# 8500_ADC_Y.net
KiCad netlist of a schematic drawn in Altium Designer
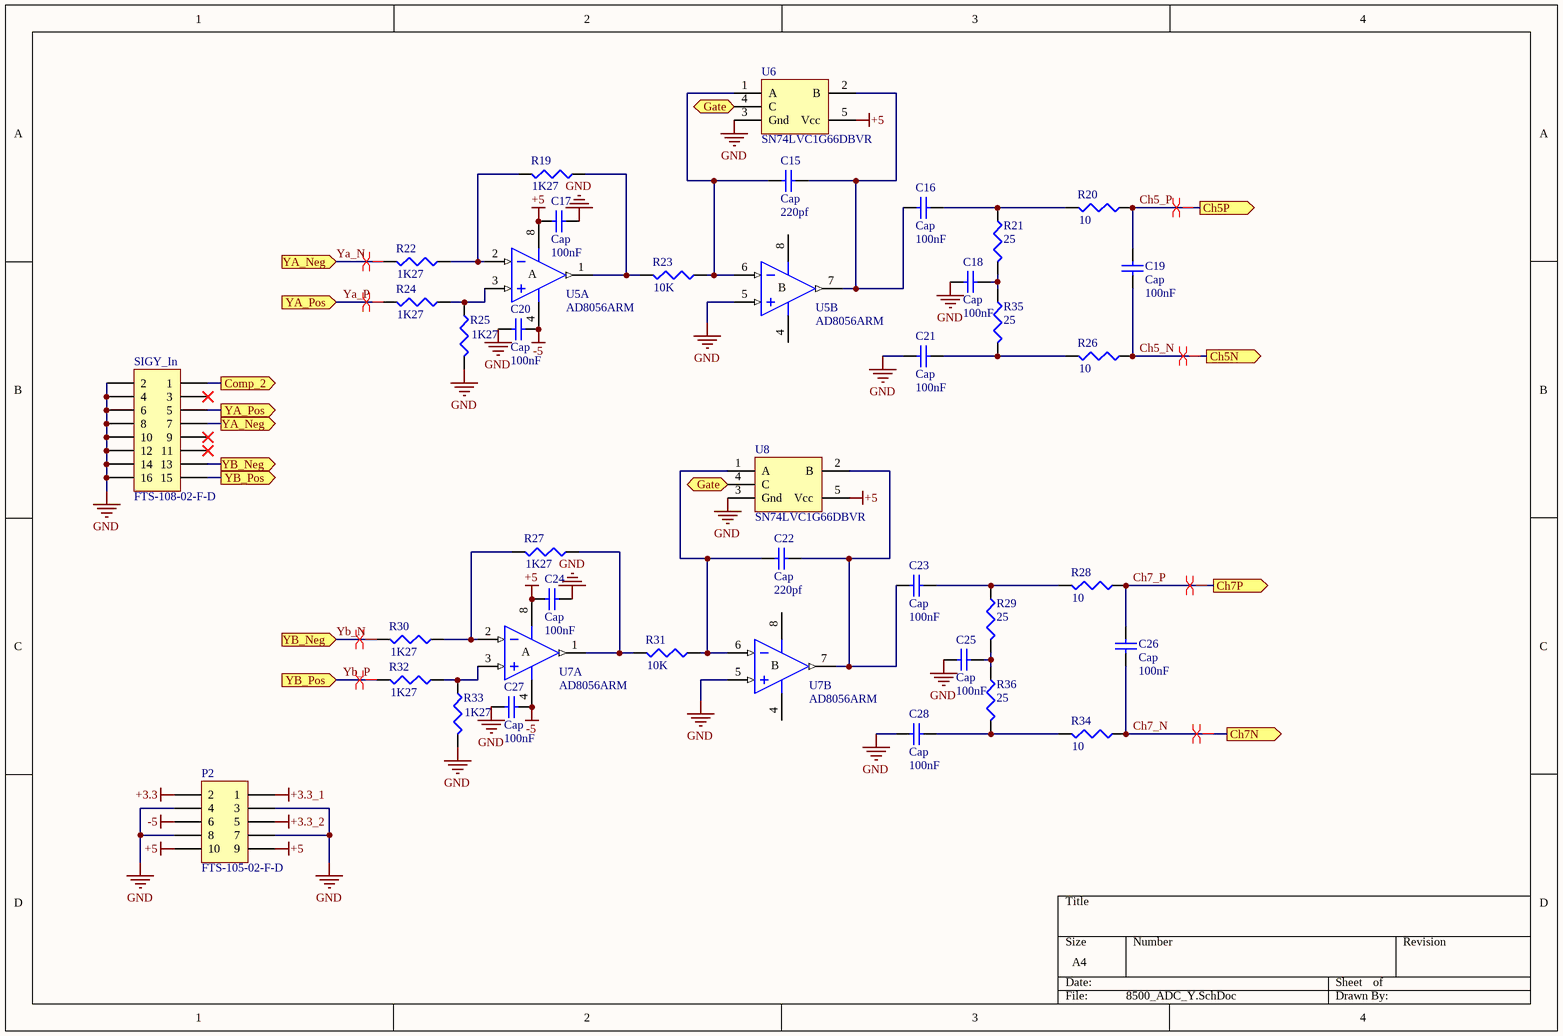
[diagram p0: 8500_ADC_Y.SchDoc]

(export (version "E")
  (design (tool "Eeschema 10.0.6"))
  (components
    (comp (ref "C15")
      (value "Cap")
      (footprint "0402")
      (description "Capacitor")
      (fields (field (name "ALTIUM_VALUE") "220pf") (field (name "PUBLISHER") "Altium Limited"))
      (libsource (lib "Miscellaneous Devices") (part "Cap"))
    )
    (comp (ref "C16")
      (value "Cap")
      (footprint "0402")
      (description "Capacitor")
      (fields (field (name "ALTIUM_VALUE") "100nF") (field (name "PUBLISHER") "Altium Limited"))
      (libsource (lib "Miscellaneous Devices") (part "Cap"))
    )
    (comp (ref "C17")
      (value "Cap")
      (footprint "0402")
      (description "Capacitor")
      (fields (field (name "ALTIUM_VALUE") "100nF") (field (name "PUBLISHER") "Altium Limited"))
      (libsource (lib "Miscellaneous Devices") (part "Cap"))
    )
    (comp (ref "C18")
      (value "Cap")
      (footprint "0402")
      (description "Capacitor")
      (fields (field (name "ALTIUM_VALUE") "100nF") (field (name "PUBLISHER") "Altium Limited"))
      (libsource (lib "Miscellaneous Devices") (part "Cap"))
    )
    (comp (ref "C19")
      (value "Cap")
      (footprint "0402")
      (description "Capacitor")
      (fields (field (name "ALTIUM_VALUE") "100nF") (field (name "PUBLISHER") "Altium Limited"))
      (libsource (lib "Miscellaneous Devices") (part "Cap"))
    )
    (comp (ref "C20")
      (value "Cap")
      (footprint "0402")
      (description "Capacitor")
      (fields (field (name "ALTIUM_VALUE") "100nF") (field (name "PUBLISHER") "Altium Limited"))
      (libsource (lib "Miscellaneous Devices") (part "Cap"))
    )
    (comp (ref "C21")
      (value "Cap")
      (footprint "0402")
      (description "Capacitor")
      (fields (field (name "ALTIUM_VALUE") "100nF") (field (name "PUBLISHER") "Altium Limited"))
      (libsource (lib "Miscellaneous Devices") (part "Cap"))
    )
    (comp (ref "C22")
      (value "Cap")
      (footprint "0402")
      (description "Capacitor")
      (fields (field (name "ALTIUM_VALUE") "220pf") (field (name "PUBLISHER") "Altium Limited"))
      (libsource (lib "Miscellaneous Devices") (part "Cap"))
    )
    (comp (ref "C23")
      (value "Cap")
      (footprint "0402")
      (description "Capacitor")
      (fields (field (name "ALTIUM_VALUE") "100nF") (field (name "PUBLISHER") "Altium Limited"))
      (libsource (lib "Miscellaneous Devices") (part "Cap"))
    )
    (comp (ref "C24")
      (value "Cap")
      (footprint "0402")
      (description "Capacitor")
      (fields (field (name "ALTIUM_VALUE") "100nF") (field (name "PUBLISHER") "Altium Limited"))
      (libsource (lib "Miscellaneous Devices") (part "Cap"))
    )
    (comp (ref "C25")
      (value "Cap")
      (footprint "0402")
      (description "Capacitor")
      (fields (field (name "ALTIUM_VALUE") "100nF") (field (name "PUBLISHER") "Altium Limited"))
      (libsource (lib "Miscellaneous Devices") (part "Cap"))
    )
    (comp (ref "C26")
      (value "Cap")
      (footprint "0402")
      (description "Capacitor")
      (fields (field (name "ALTIUM_VALUE") "100nF") (field (name "PUBLISHER") "Altium Limited"))
      (libsource (lib "Miscellaneous Devices") (part "Cap"))
    )
    (comp (ref "C27")
      (value "Cap")
      (footprint "0402")
      (description "Capacitor")
      (fields (field (name "ALTIUM_VALUE") "100nF") (field (name "PUBLISHER") "Altium Limited"))
      (libsource (lib "Miscellaneous Devices") (part "Cap"))
    )
    (comp (ref "C28")
      (value "Cap")
      (footprint "0402")
      (description "Capacitor")
      (fields (field (name "ALTIUM_VALUE") "100nF") (field (name "PUBLISHER") "Altium Limited"))
      (libsource (lib "Miscellaneous Devices") (part "Cap"))
    )
    (comp (ref "P2")
      (value "FTS-105-02-F-D")
      (footprint "MHDR2X5")
      (libsource (lib "Int_Lib1") (part "FTR-105-01-D"))
    )
    (comp (ref "R19")
      (value "1K27")
      (footprint "0402")
      (description "Resistor")
      (fields (field (name "Comment") "Res3") (field (name "PUBLISHER") "Altium Limited"))
      (libsource (lib "Miscellaneous Devices") (part "Res3"))
    )
    (comp (ref "R20")
      (value "10")
      (footprint "0402")
      (description "Resistor")
      (fields (field (name "Comment") "Res3") (field (name "PUBLISHER") "Altium Limited"))
      (libsource (lib "Miscellaneous Devices") (part "Res3"))
    )
    (comp (ref "R21")
      (value "25")
      (footprint "0402")
      (description "Resistor")
      (fields (field (name "Comment") "Res3") (field (name "PUBLISHER") "Altium Limited"))
      (libsource (lib "Miscellaneous Devices") (part "Res3"))
    )
    (comp (ref "R22")
      (value "1K27")
      (footprint "0402")
      (description "Resistor")
      (fields (field (name "Comment") "Res3") (field (name "PUBLISHER") "Altium Limited"))
      (libsource (lib "Miscellaneous Devices") (part "Res3"))
    )
    (comp (ref "R23")
      (value "10K")
      (footprint "0402")
      (description "Resistor")
      (fields (field (name "Comment") "Res3") (field (name "PUBLISHER") "Altium Limited"))
      (libsource (lib "Miscellaneous Devices") (part "Res3"))
    )
    (comp (ref "R24")
      (value "1K27")
      (footprint "0402")
      (description "Resistor")
      (fields (field (name "Comment") "Res3") (field (name "PUBLISHER") "Altium Limited"))
      (libsource (lib "Miscellaneous Devices") (part "Res3"))
    )
    (comp (ref "R25")
      (value "1K27")
      (footprint "0402")
      (description "Resistor")
      (fields (field (name "Comment") "Res3") (field (name "PUBLISHER") "Altium Limited"))
      (libsource (lib "Miscellaneous Devices") (part "Res3"))
    )
    (comp (ref "R26")
      (value "10")
      (footprint "0402")
      (description "Resistor")
      (fields (field (name "Comment") "Res3") (field (name "PUBLISHER") "Altium Limited"))
      (libsource (lib "Miscellaneous Devices") (part "Res3"))
    )
    (comp (ref "R27")
      (value "1K27")
      (footprint "0402")
      (description "Resistor")
      (fields (field (name "Comment") "Res3") (field (name "PUBLISHER") "Altium Limited"))
      (libsource (lib "Miscellaneous Devices") (part "Res3"))
    )
    (comp (ref "R28")
      (value "10")
      (footprint "0402")
      (description "Resistor")
      (fields (field (name "Comment") "Res3") (field (name "PUBLISHER") "Altium Limited"))
      (libsource (lib "Miscellaneous Devices") (part "Res3"))
    )
    (comp (ref "R29")
      (value "25")
      (footprint "0402")
      (description "Resistor")
      (fields (field (name "Comment") "Res3") (field (name "PUBLISHER") "Altium Limited"))
      (libsource (lib "Miscellaneous Devices") (part "Res3"))
    )
    (comp (ref "R30")
      (value "1K27")
      (footprint "0402")
      (description "Resistor")
      (fields (field (name "Comment") "Res3") (field (name "PUBLISHER") "Altium Limited"))
      (libsource (lib "Miscellaneous Devices") (part "Res3"))
    )
    (comp (ref "R31")
      (value "10K")
      (footprint "0402")
      (description "Resistor")
      (fields (field (name "Comment") "Res3") (field (name "PUBLISHER") "Altium Limited"))
      (libsource (lib "Miscellaneous Devices") (part "Res3"))
    )
    (comp (ref "R32")
      (value "1K27")
      (footprint "0402")
      (description "Resistor")
      (fields (field (name "Comment") "Res3") (field (name "PUBLISHER") "Altium Limited"))
      (libsource (lib "Miscellaneous Devices") (part "Res3"))
    )
    (comp (ref "R33")
      (value "1K27")
      (footprint "0402")
      (description "Resistor")
      (fields (field (name "Comment") "Res3") (field (name "PUBLISHER") "Altium Limited"))
      (libsource (lib "Miscellaneous Devices") (part "Res3"))
    )
    (comp (ref "R34")
      (value "10")
      (footprint "0402")
      (description "Resistor")
      (fields (field (name "Comment") "Res3") (field (name "PUBLISHER") "Altium Limited"))
      (libsource (lib "Miscellaneous Devices") (part "Res3"))
    )
    (comp (ref "R35")
      (value "25")
      (footprint "0402")
      (description "Resistor")
      (fields (field (name "Comment") "Res3") (field (name "PUBLISHER") "Altium Limited"))
      (libsource (lib "Miscellaneous Devices") (part "Res3"))
    )
    (comp (ref "R36")
      (value "25")
      (footprint "0402")
      (description "Resistor")
      (fields (field (name "Comment") "Res3") (field (name "PUBLISHER") "Altium Limited"))
      (libsource (lib "Miscellaneous Devices") (part "Res3"))
    )
    (comp (ref "SIGY_In")
      (value "FTS-108-02-F-D")
      (footprint "MHDR2X8")
      (libsource (lib "Int_Lib1") (part "FTR-108-01-D"))
    )
    (comp (ref "U5")
      (value "AD8056ARM")
      (footprint "RM-8")
      (description "Low Cost, 300MHz Voltage Feedback Amplifier")
      (fields (field (name "PUBLISHER") "Altium Limited"))
      (libsource (lib "AD Operational Amplifier") (part "AD8056ARM"))
    )
    (comp (ref "U6")
      (value "SN74LVC1G66DBVR")
      (footprint "SOT23-5")
      (libsource (lib "Int_Lib1") (part "SN74LVC1G66DBVR"))
    )
    (comp (ref "U7")
      (value "AD8056ARM")
      (footprint "RM-8")
      (description "Low Cost, 300MHz Voltage Feedback Amplifier")
      (fields (field (name "PUBLISHER") "Altium Limited"))
      (libsource (lib "AD Operational Amplifier") (part "AD8056ARM"))
    )
    (comp (ref "U8")
      (value "SN74LVC1G66DBVR")
      (footprint "SOT23-5")
      (libsource (lib "Int_Lib1") (part "SN74LVC1G66DBVR"))
    )
  )
  (nets
    (net (code "1") (name "+3.3") (class "Default")
      (node (ref "P2") (pin "2") (pinfunction "2_2") (pintype "passive"))
    )
    (net (code "2") (name "+3.3_1") (class "Default")
      (node (ref "P2") (pin "1") (pinfunction "1_1") (pintype "passive"))
    )
    (net (code "3") (name "+3.3_2") (class "Default")
      (node (ref "P2") (pin "5") (pinfunction "5_5") (pintype "passive"))
    )
    (net (code "4") (name "+5") (class "Default")
      (node (ref "C17") (pin "1") (pinfunction "1_1") (pintype "passive"))
      (node (ref "C24") (pin "1") (pinfunction "1_1") (pintype "passive"))
      (node (ref "P2") (pin "10") (pinfunction "10_10") (pintype "passive"))
      (node (ref "P2") (pin "9") (pinfunction "9_9") (pintype "passive"))
      (node (ref "U5") (pin "8") (pinfunction "V+_8") (pintype "power_in"))
      (node (ref "U6") (pin "5") (pinfunction "Vcc_5") (pintype "passive"))
      (node (ref "U7") (pin "8") (pinfunction "V+_8") (pintype "power_in"))
      (node (ref "U8") (pin "5") (pinfunction "Vcc_5") (pintype "passive"))
    )
    (net (code "5") (name "-5") (class "Default")
      (node (ref "C20") (pin "2") (pinfunction "2_2") (pintype "passive"))
      (node (ref "C27") (pin "2") (pinfunction "2_2") (pintype "passive"))
      (node (ref "P2") (pin "6") (pinfunction "6_6") (pintype "passive"))
      (node (ref "U5") (pin "4") (pinfunction "V-_4") (pintype "power_in"))
      (node (ref "U7") (pin "4") (pinfunction "V-_4") (pintype "power_in"))
    )
    (net (code "6") (name "/Ch5_N") (class "Default")
      (node (ref "C19") (pin "1") (pinfunction "1_1") (pintype "passive"))
      (node (ref "R26") (pin "1") (pinfunction "1_1") (pintype "passive"))
    )
    (net (code "7") (name "/Ch5_P") (class "Default")
      (node (ref "C19") (pin "2") (pinfunction "2_2") (pintype "passive"))
      (node (ref "R20") (pin "1") (pinfunction "1_1") (pintype "passive"))
    )
    (net (code "8") (name "/Ch7_N") (class "Default")
      (node (ref "C26") (pin "1") (pinfunction "1_1") (pintype "passive"))
      (node (ref "R34") (pin "1") (pinfunction "1_1") (pintype "passive"))
    )
    (net (code "9") (name "/Ch7_P") (class "Default")
      (node (ref "C26") (pin "2") (pinfunction "2_2") (pintype "passive"))
      (node (ref "R28") (pin "1") (pinfunction "1_1") (pintype "passive"))
    )
    (net (code "10") (name "/Comp_2") (class "Default")
      (node (ref "SIGY_In") (pin "1") (pinfunction "1_1") (pintype "passive"))
    )
    (net (code "11") (name "/Gate") (class "Default")
      (node (ref "U6") (pin "4") (pinfunction "C_4") (pintype "passive"))
      (node (ref "U8") (pin "4") (pinfunction "C_4") (pintype "passive"))
    )
    (net (code "12") (name "/Ya_N") (class "Default")
      (node (ref "R22") (pin "2") (pinfunction "2_2") (pintype "passive"))
      (node (ref "SIGY_In") (pin "7") (pinfunction "7_7") (pintype "passive"))
    )
    (net (code "13") (name "/Ya_P") (class "Default")
      (node (ref "R24") (pin "2") (pinfunction "2_2") (pintype "passive"))
      (node (ref "SIGY_In") (pin "5") (pinfunction "5_5") (pintype "passive"))
    )
    (net (code "14") (name "/Yb_N") (class "Default")
      (node (ref "R30") (pin "2") (pinfunction "2_2") (pintype "passive"))
      (node (ref "SIGY_In") (pin "13") (pinfunction "13_13") (pintype "passive"))
    )
    (net (code "15") (name "/Yb_P") (class "Default")
      (node (ref "R32") (pin "2") (pinfunction "2_2") (pintype "passive"))
      (node (ref "SIGY_In") (pin "15") (pinfunction "15_15") (pintype "passive"))
    )
    (net (code "16") (name "GND") (class "Default")
      (node (ref "C17") (pin "2") (pinfunction "2_2") (pintype "passive"))
      (node (ref "C18") (pin "1") (pinfunction "1_1") (pintype "passive"))
      (node (ref "C20") (pin "1") (pinfunction "1_1") (pintype "passive"))
      (node (ref "C21") (pin "1") (pinfunction "1_1") (pintype "passive"))
      (node (ref "C24") (pin "2") (pinfunction "2_2") (pintype "passive"))
      (node (ref "C25") (pin "1") (pinfunction "1_1") (pintype "passive"))
      (node (ref "C27") (pin "1") (pinfunction "1_1") (pintype "passive"))
      (node (ref "C28") (pin "1") (pinfunction "1_1") (pintype "passive"))
      (node (ref "P2") (pin "3") (pinfunction "3_3") (pintype "passive"))
      (node (ref "P2") (pin "4") (pinfunction "4_4") (pintype "passive"))
      (node (ref "P2") (pin "7") (pinfunction "7_7") (pintype "passive"))
      (node (ref "P2") (pin "8") (pinfunction "8_8") (pintype "passive"))
      (node (ref "R25") (pin "2") (pinfunction "2_2") (pintype "passive"))
      (node (ref "R33") (pin "2") (pinfunction "2_2") (pintype "passive"))
      (node (ref "SIGY_In") (pin "10") (pinfunction "10_10") (pintype "passive"))
      (node (ref "SIGY_In") (pin "12") (pinfunction "12_12") (pintype "passive"))
      (node (ref "SIGY_In") (pin "14") (pinfunction "14_14") (pintype "passive"))
      (node (ref "SIGY_In") (pin "16") (pinfunction "16_16") (pintype "passive"))
      (node (ref "SIGY_In") (pin "2") (pinfunction "2_2") (pintype "passive"))
      (node (ref "SIGY_In") (pin "4") (pinfunction "4_4") (pintype "passive"))
      (node (ref "SIGY_In") (pin "6") (pinfunction "6_6") (pintype "passive"))
      (node (ref "SIGY_In") (pin "8") (pinfunction "8_8") (pintype "passive"))
      (node (ref "U5") (pin "5") (pinfunction "IN+_5") (pintype "input"))
      (node (ref "U6") (pin "3") (pinfunction "Gnd_3") (pintype "passive"))
      (node (ref "U7") (pin "5") (pinfunction "IN+_5") (pintype "input"))
      (node (ref "U8") (pin "3") (pinfunction "Gnd_3") (pintype "passive"))
    )
    (net (code "17") (name "Net-(C16-Pad2)") (class "Default")
      (node (ref "C16") (pin "2") (pinfunction "2_2") (pintype "passive"))
      (node (ref "R20") (pin "2") (pinfunction "2_2") (pintype "passive"))
      (node (ref "R21") (pin "1") (pinfunction "1_1") (pintype "passive"))
    )
    (net (code "18") (name "Net-(C18-Pad2)") (class "Default")
      (node (ref "C18") (pin "2") (pinfunction "2_2") (pintype "passive"))
      (node (ref "R21") (pin "2") (pinfunction "2_2") (pintype "passive"))
      (node (ref "R35") (pin "1") (pinfunction "1_1") (pintype "passive"))
    )
    (net (code "19") (name "Net-(C21-Pad2)") (class "Default")
      (node (ref "C21") (pin "2") (pinfunction "2_2") (pintype "passive"))
      (node (ref "R26") (pin "2") (pinfunction "2_2") (pintype "passive"))
      (node (ref "R35") (pin "2") (pinfunction "2_2") (pintype "passive"))
    )
    (net (code "20") (name "Net-(C23-Pad2)") (class "Default")
      (node (ref "C23") (pin "2") (pinfunction "2_2") (pintype "passive"))
      (node (ref "R28") (pin "2") (pinfunction "2_2") (pintype "passive"))
      (node (ref "R29") (pin "1") (pinfunction "1_1") (pintype "passive"))
    )
    (net (code "21") (name "Net-(C25-Pad2)") (class "Default")
      (node (ref "C25") (pin "2") (pinfunction "2_2") (pintype "passive"))
      (node (ref "R29") (pin "2") (pinfunction "2_2") (pintype "passive"))
      (node (ref "R36") (pin "1") (pinfunction "1_1") (pintype "passive"))
    )
    (net (code "22") (name "Net-(C28-Pad2)") (class "Default")
      (node (ref "C28") (pin "2") (pinfunction "2_2") (pintype "passive"))
      (node (ref "R34") (pin "2") (pinfunction "2_2") (pintype "passive"))
      (node (ref "R36") (pin "2") (pinfunction "2_2") (pintype "passive"))
    )
    (net (code "23") (name "Net-(U5A-IN+)") (class "Default")
      (node (ref "R24") (pin "1") (pinfunction "1_1") (pintype "passive"))
      (node (ref "R25") (pin "1") (pinfunction "1_1") (pintype "passive"))
      (node (ref "U5") (pin "3") (pinfunction "IN+_3") (pintype "input"))
    )
    (net (code "24") (name "Net-(U5A-IN-)") (class "Default")
      (node (ref "R19") (pin "2") (pinfunction "2_2") (pintype "passive"))
      (node (ref "R22") (pin "1") (pinfunction "1_1") (pintype "passive"))
      (node (ref "U5") (pin "2") (pinfunction "IN-_2") (pintype "input"))
    )
    (net (code "25") (name "Net-(U5A-OUT)") (class "Default")
      (node (ref "R19") (pin "1") (pinfunction "1_1") (pintype "passive"))
      (node (ref "R23") (pin "2") (pinfunction "2_2") (pintype "passive"))
      (node (ref "U5") (pin "1") (pinfunction "OUT_1") (pintype "output"))
    )
    (net (code "26") (name "Net-(U5B-IN-)") (class "Default")
      (node (ref "C15") (pin "1") (pinfunction "1_1") (pintype "passive"))
      (node (ref "R23") (pin "1") (pinfunction "1_1") (pintype "passive"))
      (node (ref "U5") (pin "6") (pinfunction "IN-_6") (pintype "input"))
      (node (ref "U6") (pin "1") (pinfunction "A_1") (pintype "passive"))
    )
    (net (code "27") (name "Net-(U5B-OUT)") (class "Default")
      (node (ref "C15") (pin "2") (pinfunction "2_2") (pintype "passive"))
      (node (ref "C16") (pin "1") (pinfunction "1_1") (pintype "passive"))
      (node (ref "U5") (pin "7") (pinfunction "OUT_7") (pintype "output"))
      (node (ref "U6") (pin "2") (pinfunction "B_2") (pintype "passive"))
    )
    (net (code "28") (name "Net-(U7A-IN+)") (class "Default")
      (node (ref "R32") (pin "1") (pinfunction "1_1") (pintype "passive"))
      (node (ref "R33") (pin "1") (pinfunction "1_1") (pintype "passive"))
      (node (ref "U7") (pin "3") (pinfunction "IN+_3") (pintype "input"))
    )
    (net (code "29") (name "Net-(U7A-IN-)") (class "Default")
      (node (ref "R27") (pin "2") (pinfunction "2_2") (pintype "passive"))
      (node (ref "R30") (pin "1") (pinfunction "1_1") (pintype "passive"))
      (node (ref "U7") (pin "2") (pinfunction "IN-_2") (pintype "input"))
    )
    (net (code "30") (name "Net-(U7A-OUT)") (class "Default")
      (node (ref "R27") (pin "1") (pinfunction "1_1") (pintype "passive"))
      (node (ref "R31") (pin "2") (pinfunction "2_2") (pintype "passive"))
      (node (ref "U7") (pin "1") (pinfunction "OUT_1") (pintype "output"))
    )
    (net (code "31") (name "Net-(U7B-IN-)") (class "Default")
      (node (ref "C22") (pin "1") (pinfunction "1_1") (pintype "passive"))
      (node (ref "R31") (pin "1") (pinfunction "1_1") (pintype "passive"))
      (node (ref "U7") (pin "6") (pinfunction "IN-_6") (pintype "input"))
      (node (ref "U8") (pin "1") (pinfunction "A_1") (pintype "passive"))
    )
    (net (code "32") (name "Net-(U7B-OUT)") (class "Default")
      (node (ref "C22") (pin "2") (pinfunction "2_2") (pintype "passive"))
      (node (ref "C23") (pin "1") (pinfunction "1_1") (pintype "passive"))
      (node (ref "U7") (pin "7") (pinfunction "OUT_7") (pintype "output"))
      (node (ref "U8") (pin "2") (pinfunction "B_2") (pintype "passive"))
    )
    (net (code "33") (name "unconnected-(SIGY_In-Pad3)") (class "Default")
      (node (ref "SIGY_In") (pin "3") (pinfunction "3_3") (pintype "passive+no_connect"))
    )
    (net (code "34") (name "unconnected-(SIGY_In-Pad9)") (class "Default")
      (node (ref "SIGY_In") (pin "9") (pinfunction "9_9") (pintype "passive+no_connect"))
    )
    (net (code "35") (name "unconnected-(SIGY_In-Pad11)") (class "Default")
      (node (ref "SIGY_In") (pin "11") (pinfunction "11_11") (pintype "passive+no_connect"))
    )
    (net (code "36") (name "unconnected-(U5B-V+-Pad8)") (class "Default")
      (node (ref "U5") (pin "8") (pinfunction "V+_8") (pintype "power_in"))
    )
    (net (code "37") (name "unconnected-(U5B-V--Pad4)") (class "Default")
      (node (ref "U5") (pin "4") (pinfunction "V-_4") (pintype "power_in"))
    )
    (net (code "38") (name "unconnected-(U7B-V+-Pad8)") (class "Default")
      (node (ref "U7") (pin "8") (pinfunction "V+_8") (pintype "power_in"))
    )
    (net (code "39") (name "unconnected-(U7B-V--Pad4)") (class "Default")
      (node (ref "U7") (pin "4") (pinfunction "V-_4") (pintype "power_in"))
    )
  )
)
